# BUCK_5v_TPS54340_P-MOS.net
KiCad netlist of a schematic drawn in Altium Designer
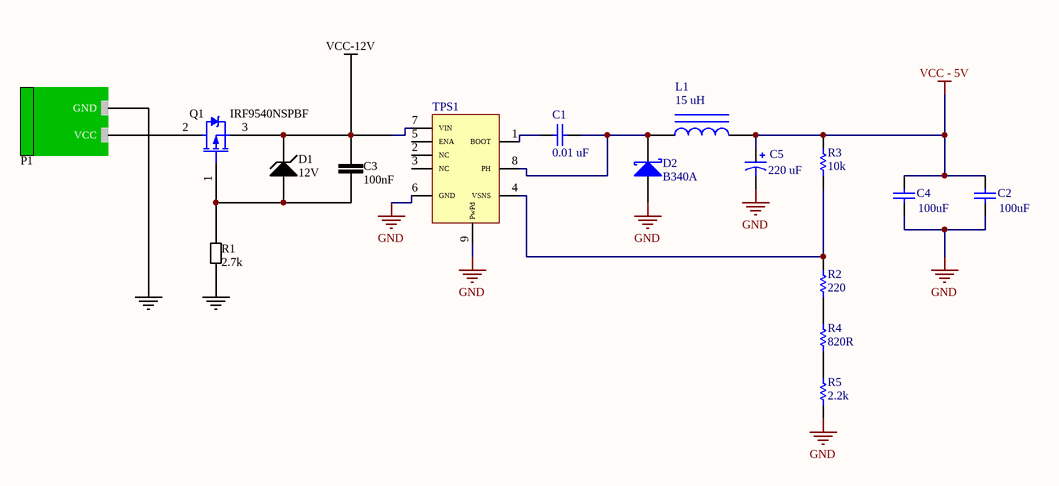
[diagram p0: BUCK_5v_TPS54340_P-MOS.SchDoc]

(export (version "E")
  (design (tool "Eeschema 10.0.6"))
  (components
    (comp (ref "C1")
      (value "0.01 uF")
      (footprint "RAD-0.3")
      (description "Capacitor")
      (fields (field (name "PUBLISHER") "Altium Limited"))
      (libsource (lib "Miscellaneous Devices") (part "Cap"))
    )
    (comp (ref "C2")
      (value "100uF")
      (footprint "RAD-0.3")
      (description "Capacitor")
      (fields (field (name "PUBLISHER") "Altium Limited"))
      (libsource (lib "Miscellaneous Devices") (part "Cap"))
    )
    (comp (ref "C3")
      (value "100nF")
      (footprint "CER_0805")
      (description "CAP CER 100n 50V X7R 10% 0805")
      (libsource (lib "Capacitors") (part "00002105"))
    )
    (comp (ref "C4")
      (value "100uF")
      (footprint "RAD-0.3")
      (description "Capacitor")
      (fields (field (name "PUBLISHER") "Altium Limited"))
      (libsource (lib "Miscellaneous Devices") (part "Cap"))
    )
    (comp (ref "C5")
      (value "220 uF")
      (footprint "RB7.6-15")
      (description "Polarized Capacitor (Radial)")
      (fields (field (name "PUBLISHER") "Altium Limited"))
      (libsource (lib "Miscellaneous Devices") (part "Cap Pol1"))
    )
    (comp (ref "D1")
      (value "12V")
      (footprint "DO214AC")
      (description "DIODE ZENER")
      (fields
        (field (name "MANUFACTURER") "Vishay Semiconductor Diodes Division")
        (field (name "MANUFACTURER PART NUMBER") "B360B")
      )
      (libsource (lib "Discrete_Semiconductor") (part "ZENER"))
    )
    (comp (ref "D2")
      (value "B340A")
      (footprint "SMB")
      (description "Schottky Diode")
      (fields (field (name "PUBLISHER") "Altium Limited"))
      (libsource (lib "Miscellaneous Devices") (part "D Schottky"))
    )
    (comp (ref "L1")
      (value "15 uH")
      (footprint "AXIAL-0.9")
      (description "Magnetic-Core Inductor")
      (fields (field (name "PUBLISHER") "Altium Limited"))
      (libsource (lib "Miscellaneous Devices") (part "Inductor Iron"))
    )
    (comp (ref "P1")
      (value "2EDGRC-5.08-02P-14-00A(H)")
      (footprint "PWR_Con")
      (description "TERM BLOCK HDR 2POS 90DEG 5.08MM")
      (libsource (lib "Electro_Mechanical") (part "00000002"))
    )
    (comp (ref "Q1")
      (value "IRF9540NSPBF")
      (footprint "D2PAK-2")
      (description "P-MOS")
      (fields (field (name "MANUFACTURER") "INTERNATIONAL RECTIFIER"))
      (libsource (lib "Discrete_Semiconductor") (part "IRF9540N"))
    )
    (comp (ref "R1")
      (value "2.7k")
      (footprint "RESC2013X38N-0805-NOOVERLAY")
      (description "RES SMD 2.7 kOhm 1/8W 0805")
      (fields (field (name "POWER") "0.125W, 1/8W"))
      (libsource (lib "Resistors") (part "00002701"))
    )
    (comp (ref "R2")
      (value "220")
      (footprint "AXIAL-0.3")
      (description "Resistor")
      (fields (field (name "PUBLISHER") "Altium Limited"))
      (libsource (lib "Miscellaneous Devices") (part "Res1"))
    )
    (comp (ref "R3")
      (value "10k")
      (footprint "AXIAL-0.3")
      (description "Resistor")
      (fields (field (name "PUBLISHER") "Altium Limited"))
      (libsource (lib "Miscellaneous Devices") (part "Res1"))
    )
    (comp (ref "R4")
      (value "820R")
      (footprint "AXIAL-0.3")
      (description "Resistor")
      (fields (field (name "PUBLISHER") "Altium Limited"))
      (libsource (lib "Miscellaneous Devices") (part "Res1"))
    )
    (comp (ref "R5")
      (value "2.2k")
      (footprint "AXIAL-0.3")
      (description "Resistor")
      (fields (field (name "PUBLISHER") "Altium Limited"))
      (libsource (lib "Miscellaneous Devices") (part "Res1"))
    )
    (comp (ref "TPS1")
      (value "~")
      (footprint "TPS5430")
      (description "TPS5430")
      (libsource (lib "Schlib2_TPS5430") (part "Component_1"))
    )
  )
  (nets
    (net (code "1") (name "GND") (class "Default")
      (node (ref "C2") (pin "1") (pinfunction "1_1") (pintype "passive"))
      (node (ref "C4") (pin "1") (pinfunction "1_1") (pintype "passive"))
      (node (ref "C5") (pin "2") (pinfunction "2_2") (pintype "passive"))
      (node (ref "D2") (pin "1") (pinfunction "A_1") (pintype "passive"))
      (node (ref "P1") (pin "1") (pinfunction "GND_1") (pintype "passive"))
      (node (ref "R1") (pin "1") (pinfunction "1_1") (pintype "passive"))
      (node (ref "R5") (pin "1") (pinfunction "1_1") (pintype "passive"))
      (node (ref "TPS1") (pin "6") (pinfunction "GND_6") (pintype "passive"))
      (node (ref "TPS1") (pin "9") (pinfunction "PwPd_9") (pintype "passive"))
    )
    (net (code "2") (name "Net-(D1-Anode)") (class "Default")
      (node (ref "C3") (pin "1") (pinfunction "1_1") (pintype "passive"))
      (node (ref "D1") (pin "2") (pinfunction "Anode_2") (pintype "passive"))
      (node (ref "Q1") (pin "1") (pinfunction "G_1") (pintype "passive"))
      (node (ref "R1") (pin "2") (pinfunction "2_2") (pintype "passive"))
    )
    (net (code "3") (name "Net-(D2-K)") (class "Default")
      (node (ref "C1") (pin "2") (pinfunction "2_2") (pintype "passive"))
      (node (ref "D2") (pin "2") (pinfunction "K_2") (pintype "passive"))
      (node (ref "L1") (pin "1") (pinfunction "1_1") (pintype "passive"))
      (node (ref "TPS1") (pin "8") (pinfunction "PH_8") (pintype "passive"))
    )
    (net (code "4") (name "Net-(P1-VCC)") (class "Default")
      (node (ref "P1") (pin "2") (pinfunction "VCC_2") (pintype "passive"))
      (node (ref "Q1") (pin "2") (pinfunction "D_2") (pintype "passive"))
    )
    (net (code "5") (name "Net-(R2-Pad1)") (class "Default")
      (node (ref "R2") (pin "1") (pinfunction "1_1") (pintype "passive"))
      (node (ref "R4") (pin "2") (pinfunction "2_2") (pintype "passive"))
    )
    (net (code "6") (name "Net-(R4-Pad1)") (class "Default")
      (node (ref "R4") (pin "1") (pinfunction "1_1") (pintype "passive"))
      (node (ref "R5") (pin "2") (pinfunction "2_2") (pintype "passive"))
    )
    (net (code "7") (name "Net-(TPS1-BOOT)") (class "Default")
      (node (ref "C1") (pin "1") (pinfunction "1_1") (pintype "passive"))
      (node (ref "TPS1") (pin "1") (pinfunction "BOOT_1") (pintype "passive"))
    )
    (net (code "8") (name "Net-(TPS1-VSNS)") (class "Default")
      (node (ref "R2") (pin "2") (pinfunction "2_2") (pintype "passive"))
      (node (ref "R3") (pin "1") (pinfunction "1_1") (pintype "passive"))
      (node (ref "TPS1") (pin "4") (pinfunction "VSNS_4") (pintype "passive"))
    )
    (net (code "9") (name "VCC - 5V") (class "Default")
      (node (ref "C2") (pin "2") (pinfunction "2_2") (pintype "passive"))
      (node (ref "C4") (pin "2") (pinfunction "2_2") (pintype "passive"))
      (node (ref "C5") (pin "1") (pinfunction "1_1") (pintype "passive"))
      (node (ref "L1") (pin "2") (pinfunction "2_2") (pintype "passive"))
      (node (ref "R3") (pin "2") (pinfunction "2_2") (pintype "passive"))
    )
    (net (code "10") (name "VCC-12V") (class "Default")
      (node (ref "C3") (pin "2") (pinfunction "2_2") (pintype "passive"))
      (node (ref "D1") (pin "1") (pinfunction "Cathode_1") (pintype "passive"))
      (node (ref "Q1") (pin "3") (pinfunction "S_3") (pintype "passive"))
      (node (ref "TPS1") (pin "7") (pinfunction "VIN_7") (pintype "passive"))
    )
    (net (code "11") (name "unconnected-(TPS1-ENA-Pad5)") (class "Default")
      (node (ref "TPS1") (pin "5") (pinfunction "ENA_5") (pintype "passive"))
    )
    (net (code "12") (name "unconnected-(TPS1-NC-Pad2)") (class "Default")
      (node (ref "TPS1") (pin "2") (pinfunction "NC_2") (pintype "passive"))
    )
    (net (code "13") (name "unconnected-(TPS1-NC-Pad3)") (class "Default")
      (node (ref "TPS1") (pin "3") (pinfunction "NC_3") (pintype "passive"))
    )
  )
)
